# I2C_Board.net
KiCad netlist of a schematic drawn in Altium Designer
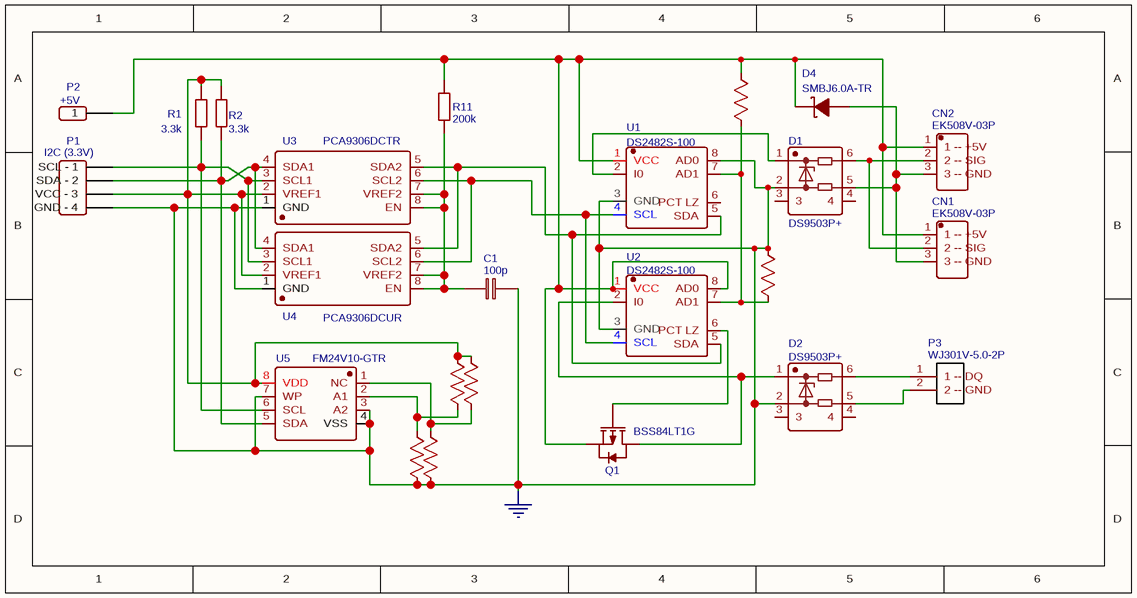
[diagram p0: I2C_Board.schdoc]

(export (version "E")
  (design (tool "Eeschema 10.0.6"))
  (components
    (comp (ref "A0")
      (value "0")
      (fields (field (name "BOM_MANUFACTURER PART") "?"))
      (libsource (lib "altium-import") (part "root_1__"))
    )
    (comp (ref "A1")
      (value "0")
      (fields (field (name "BOM_MANUFACTURER PART") "?"))
      (libsource (lib "altium-import") (part "root_1__"))
    )
    (comp (ref "AD1")
      (value "0")
      (fields (field (name "BOM_MANUFACTURER PART") "?"))
      (libsource (lib "altium-import") (part "root_1__"))
    )
    (comp (ref "AD_1")
      (value "0")
      (fields (field (name "BOM_MANUFACTURER PART") "?"))
      (libsource (lib "altium-import") (part "root_1__"))
    )
    (comp (ref "A_0")
      (value "0")
      (fields (field (name "BOM_MANUFACTURER PART") "?"))
      (libsource (lib "altium-import") (part "root_1__"))
    )
    (comp (ref "A_1")
      (value "0")
      (fields (field (name "BOM_MANUFACTURER PART") "?"))
      (libsource (lib "altium-import") (part "root_1__"))
    )
    (comp (ref "C1")
      (value "100p")
      (fields (field (name "BOM_MANUFACTURER PART") "?"))
      (libsource (lib "") (part "root_1___1"))
    )
    (comp (ref "CN1") (value "EK508V-03P") (libsource (lib "") (part "root_0___2")))
    (comp (ref "CN2") (value "EK508V-03P") (libsource (lib "") (part "root_0___2")))
    (comp (ref "D1")
      (value "DS9503P+")
      (fields (field (name "CONTRIBUTOR") "LCSC"))
      (libsource (lib "") (part "root_0___4"))
    )
    (comp (ref "D2")
      (value "DS9503P+")
      (fields (field (name "CONTRIBUTOR") "LCSC"))
      (libsource (lib "") (part "root_0___4"))
    )
    (comp (ref "D4")
      (value "SMBJ6.0A-TR")
      (fields (field (name "CONTRIBUTOR") "LCSC"))
      (libsource (lib "altium-import") (part "root_2__"))
    )
    (comp (ref "P1")
      (value "I2C (3.3V)")
      (fields (field (name "BOM_MANUFACTURER PART") "Headers??Pins 1*4P"))
      (libsource (lib "") (part "root_0___6"))
    )
    (comp (ref "P2")
      (value "+5V")
      (fields (field (name "BOM_MANUFACTURER PART") "Header 1*1P"))
      (libsource (lib "") (part "root_0___5"))
    )
    (comp (ref "P3") (value "WJ301V-5.0-2P") (libsource (lib "altium-import") (part "root_3__")))
    (comp (ref "Q1") (value "BSS84LT1G") (libsource (lib "") (part "root_3___1")))
    (comp (ref "R1")
      (value "3.3k")
      (fields (field (name "BOM_MANUFACTURER PART") "?"))
      (libsource (lib "") (part "root_1___2"))
    )
    (comp (ref "R2")
      (value "3.3k")
      (fields (field (name "BOM_MANUFACTURER PART") "?"))
      (libsource (lib "") (part "root_1___2"))
    )
    (comp (ref "R11")
      (value "200k")
      (fields (field (name "BOM_MANUFACTURER PART") "?"))
      (libsource (lib "") (part "root_3___2"))
    )
    (comp (ref "U1")
      (value "DS2482S-100")
      (fields (field (name "BOM_MANUFACTURER PART") "DS2482S-100+T&R") (field (name "CONTRIBUTOR") "LCSC"))
      (libsource (lib "") (part "root_0___3"))
    )
    (comp (ref "U2")
      (value "DS2482S-100")
      (fields (field (name "BOM_MANUFACTURER PART") "DS2482S-100+T&R") (field (name "CONTRIBUTOR") "LCSC"))
      (libsource (lib "") (part "root_0___3"))
    )
    (comp (ref "U3")
      (value "PCA9306DCTR")
      (fields (field (name "BOM_MANUFACTURER PART") "?"))
      (libsource (lib "") (part "root_0___1"))
    )
    (comp (ref "U4") (value "PCA9306DCUR") (libsource (lib "") (part "root_0___1")))
    (comp (ref "U5") (value "FM24V10-GTR") (libsource (lib "altium-import") (part "root_0__")))
  )
  (nets
    (net (code "1") (name "GND") (class "Default")
      (node (ref "AD_1") (pin "2") (pinfunction "2_2") (pintype "passive"))
      (node (ref "A_0") (pin "1") (pinfunction "1_1") (pintype "passive"))
      (node (ref "A_1") (pin "1") (pinfunction "1_1") (pintype "passive"))
      (node (ref "C1") (pin "2") (pinfunction "2_2") (pintype "passive"))
      (node (ref "D1") (pin "2") (pinfunction "P$2_2") (pintype "passive"))
      (node (ref "D2") (pin "2") (pinfunction "P$2_2") (pintype "passive"))
      (node (ref "P1") (pin "4") (pinfunction "GND_-_4_4") (pintype "passive"))
      (node (ref "U1") (pin "3") (pinfunction "GND_3") (pintype "passive"))
      (node (ref "U1") (pin "8") (pinfunction "AD0_8") (pintype "passive"))
      (node (ref "U2") (pin "3") (pinfunction "GND_3") (pintype "passive"))
      (node (ref "U3") (pin "1") (pinfunction "GND_1") (pintype "passive"))
      (node (ref "U4") (pin "1") (pinfunction "GND_1") (pintype "passive"))
      (node (ref "U5") (pin "3") (pinfunction "A2_3") (pintype "passive"))
      (node (ref "U5") (pin "4") (pinfunction "VSS_4") (pintype "passive"))
      (node (ref "U5") (pin "7") (pinfunction "WP_7") (pintype "passive"))
    )
    (net (code "2") (name "Net-(CN1-1_--_+5V)") (class "Default")
      (node (ref "AD1") (pin "2") (pinfunction "2_2") (pintype "passive"))
      (node (ref "CN1") (pin "1") (pinfunction "1_--_+5V_1") (pintype "passive"))
      (node (ref "CN2") (pin "1") (pinfunction "1_--_+5V_1") (pintype "passive"))
      (node (ref "D4") (pin "2") (pinfunction "K_2") (pintype "passive"))
      (node (ref "P2") (pin "1") (pinfunction "1_1") (pintype "passive"))
      (node (ref "Q1") (pin "2") (pinfunction "S_2") (pintype "passive"))
      (node (ref "R11") (pin "1") (pinfunction "1_1") (pintype "passive"))
      (node (ref "U1") (pin "1") (pinfunction "VCC_1") (pintype "passive"))
      (node (ref "U2") (pin "1") (pinfunction "VCC_1") (pintype "passive"))
      (node (ref "U2") (pin "8") (pinfunction "AD0_8") (pintype "passive"))
    )
    (net (code "3") (name "Net-(CN1-2_--_SIG)") (class "Default")
      (node (ref "CN1") (pin "2") (pinfunction "2_--_SIG_2") (pintype "passive"))
      (node (ref "CN2") (pin "2") (pinfunction "2_--_SIG_2") (pintype "passive"))
      (node (ref "D1") (pin "6") (pinfunction "P$4_6") (pintype "passive"))
    )
    (net (code "4") (name "Net-(CN1-3_--_GND)") (class "Default")
      (node (ref "CN1") (pin "3") (pinfunction "3_--_GND_3") (pintype "passive"))
      (node (ref "CN2") (pin "3") (pinfunction "3_--_GND_3") (pintype "passive"))
      (node (ref "D1") (pin "5") (pinfunction "P$3_5") (pintype "passive"))
      (node (ref "D4") (pin "1") (pinfunction "A_1") (pintype "passive"))
    )
    (net (code "5") (name "Net-(D1-P$1)") (class "Default")
      (node (ref "D1") (pin "1") (pinfunction "P$1_1") (pintype "passive"))
      (node (ref "U1") (pin "2") (pinfunction "I0_2") (pintype "passive"))
    )
    (net (code "6") (name "Net-(D2-P$1)") (class "Default")
      (node (ref "D2") (pin "1") (pinfunction "P$1_1") (pintype "passive"))
      (node (ref "Q1") (pin "3") (pinfunction "D_3") (pintype "passive"))
      (node (ref "U2") (pin "2") (pinfunction "I0_2") (pintype "passive"))
    )
    (net (code "7") (name "Net-(D2-P$3)") (class "Default")
      (node (ref "D2") (pin "5") (pinfunction "P$3_5") (pintype "passive"))
      (node (ref "P3") (pin "2") (pinfunction "2_--_GND_2") (pintype "passive"))
    )
    (net (code "8") (name "Net-(D2-P$4)") (class "Default")
      (node (ref "D2") (pin "6") (pinfunction "P$4_6") (pintype "passive"))
      (node (ref "P3") (pin "1") (pinfunction "1_--_DQ_1") (pintype "passive"))
    )
    (net (code "9") (name "Net-(P1-SCL_-_1)") (class "Default")
      (node (ref "P1") (pin "1") (pinfunction "SCL_-_1_1") (pintype "passive"))
      (node (ref "R1") (pin "1") (pinfunction "1_1") (pintype "passive"))
      (node (ref "U3") (pin "3") (pinfunction "SCL1_3") (pintype "passive"))
      (node (ref "U4") (pin "3") (pinfunction "SCL1_3") (pintype "passive"))
      (node (ref "U5") (pin "6") (pinfunction "SCL_6") (pintype "passive"))
    )
    (net (code "10") (name "Net-(P1-SDA_-_2)") (class "Default")
      (node (ref "P1") (pin "2") (pinfunction "SDA_-_2_2") (pintype "passive"))
      (node (ref "R2") (pin "1") (pinfunction "1_1") (pintype "passive"))
      (node (ref "U3") (pin "4") (pinfunction "SDA1_4") (pintype "passive"))
      (node (ref "U4") (pin "4") (pinfunction "SDA1_4") (pintype "passive"))
      (node (ref "U5") (pin "5") (pinfunction "SDA_5") (pintype "passive"))
    )
    (net (code "11") (name "Net-(P1-VCC_-_3)") (class "Default")
      (node (ref "A0") (pin "2") (pinfunction "2_2") (pintype "passive"))
      (node (ref "A1") (pin "2") (pinfunction "2_2") (pintype "passive"))
      (node (ref "P1") (pin "3") (pinfunction "VCC_-_3_3") (pintype "passive"))
      (node (ref "R1") (pin "2") (pinfunction "2_2") (pintype "passive"))
      (node (ref "R2") (pin "2") (pinfunction "2_2") (pintype "passive"))
      (node (ref "U3") (pin "2") (pinfunction "VREF1_2") (pintype "passive"))
      (node (ref "U4") (pin "2") (pinfunction "VREF1_2") (pintype "passive"))
      (node (ref "U5") (pin "8") (pinfunction "VDD_8") (pintype "passive"))
    )
    (net (code "12") (name "Net-(Q1-G)") (class "Default")
      (node (ref "Q1") (pin "1") (pinfunction "G_1") (pintype "passive"))
      (node (ref "U2") (pin "6") (pinfunction "PCT_LZ_6") (pintype "passive"))
    )
    (net (code "13") (name "Net-(U1-AD1)") (class "Default")
      (node (ref "AD1") (pin "1") (pinfunction "1_1") (pintype "passive"))
      (node (ref "AD_1") (pin "1") (pinfunction "1_1") (pintype "passive"))
      (node (ref "U1") (pin "7") (pinfunction "AD1_7") (pintype "passive"))
      (node (ref "U2") (pin "7") (pinfunction "AD1_7") (pintype "passive"))
    )
    (net (code "14") (name "Net-(U1-SCL)") (class "Default")
      (node (ref "U1") (pin "4") (pinfunction "SCL_4") (pintype "passive"))
      (node (ref "U2") (pin "4") (pinfunction "SCL_4") (pintype "passive"))
      (node (ref "U3") (pin "6") (pinfunction "SCL2_6") (pintype "passive"))
      (node (ref "U4") (pin "6") (pinfunction "SCL2_6") (pintype "passive"))
    )
    (net (code "15") (name "Net-(U1-SDA)") (class "Default")
      (node (ref "U1") (pin "5") (pinfunction "SDA_5") (pintype "passive"))
      (node (ref "U2") (pin "5") (pinfunction "SDA_5") (pintype "passive"))
      (node (ref "U3") (pin "5") (pinfunction "SDA2_5") (pintype "passive"))
      (node (ref "U4") (pin "5") (pinfunction "SDA2_5") (pintype "passive"))
    )
    (net (code "16") (name "Net-(U3-EN)") (class "Default")
      (node (ref "C1") (pin "1") (pinfunction "1_1") (pintype "passive"))
      (node (ref "R11") (pin "2") (pinfunction "2_2") (pintype "passive"))
      (node (ref "U3") (pin "7") (pinfunction "VREF2_7") (pintype "passive"))
      (node (ref "U3") (pin "8") (pinfunction "EN_8") (pintype "passive"))
      (node (ref "U4") (pin "7") (pinfunction "VREF2_7") (pintype "passive"))
      (node (ref "U4") (pin "8") (pinfunction "EN_8") (pintype "passive"))
    )
    (net (code "17") (name "Net-(U5-A1)") (class "Default")
      (node (ref "A1") (pin "1") (pinfunction "1_1") (pintype "passive"))
      (node (ref "A_1") (pin "2") (pinfunction "2_2") (pintype "passive"))
      (node (ref "U5") (pin "2") (pinfunction "A1_2") (pintype "passive"))
    )
    (net (code "18") (name "Net-(U5-NC)") (class "Default")
      (node (ref "A0") (pin "1") (pinfunction "1_1") (pintype "passive"))
      (node (ref "A_0") (pin "2") (pinfunction "2_2") (pintype "passive"))
      (node (ref "U5") (pin "1") (pinfunction "NC_1") (pintype "passive"))
    )
    (net (code "19") (name "unconnected-(D1-Pad3)") (class "Default")
      (node (ref "D1") (pin "3") (pinfunction "3_3") (pintype "passive"))
    )
    (net (code "20") (name "unconnected-(D1-Pad4)") (class "Default")
      (node (ref "D1") (pin "4") (pinfunction "4_4") (pintype "passive"))
    )
    (net (code "21") (name "unconnected-(D2-Pad3)") (class "Default")
      (node (ref "D2") (pin "3") (pinfunction "3_3") (pintype "passive"))
    )
    (net (code "22") (name "unconnected-(D2-Pad4)") (class "Default")
      (node (ref "D2") (pin "4") (pinfunction "4_4") (pintype "passive"))
    )
    (net (code "23") (name "unconnected-(U1-PCT_LZ-Pad6)") (class "Default")
      (node (ref "U1") (pin "6") (pinfunction "PCT_LZ_6") (pintype "passive"))
    )
  )
)
